# no_name.net
KiCad netlist of a schematic drawn in Altium Designer
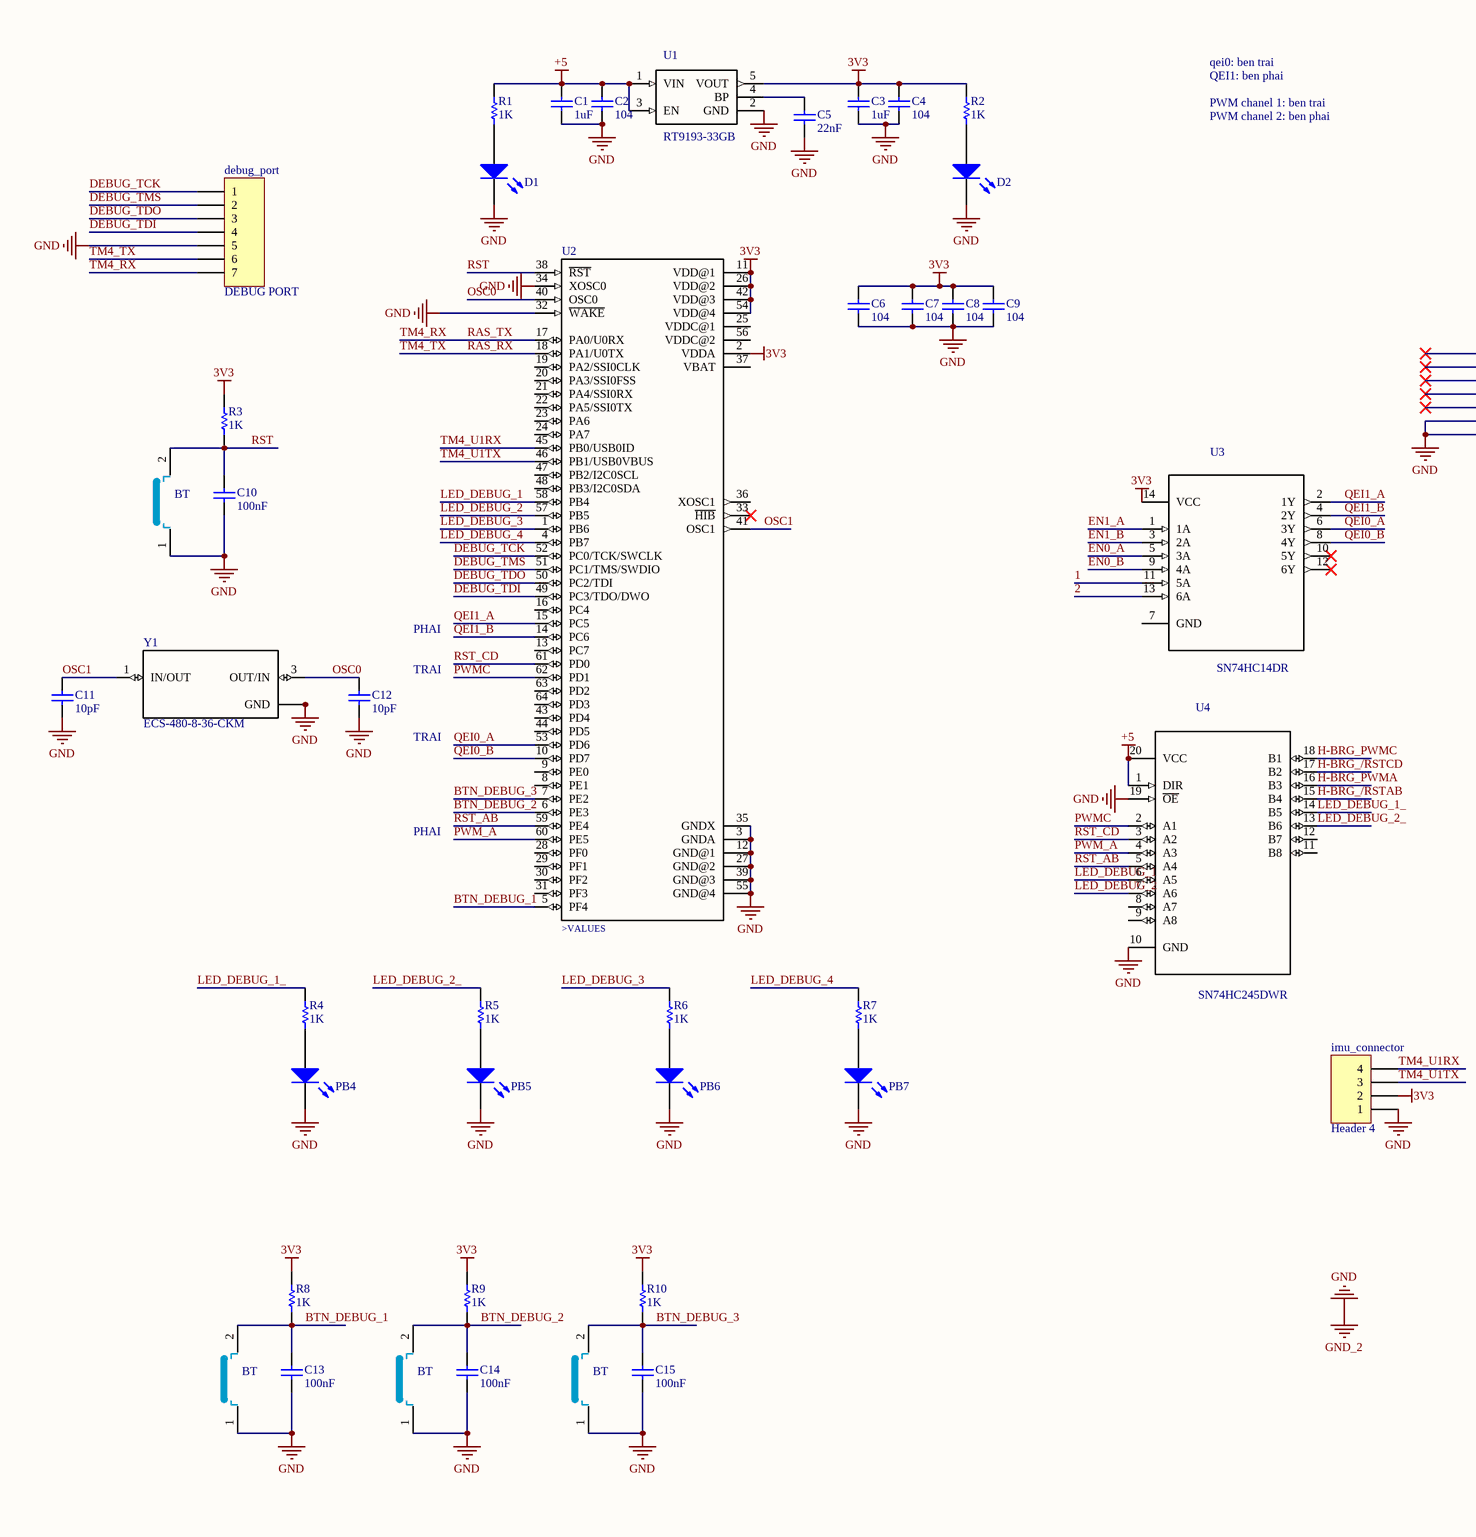
[diagram p0: no_name.SchDoc, left]
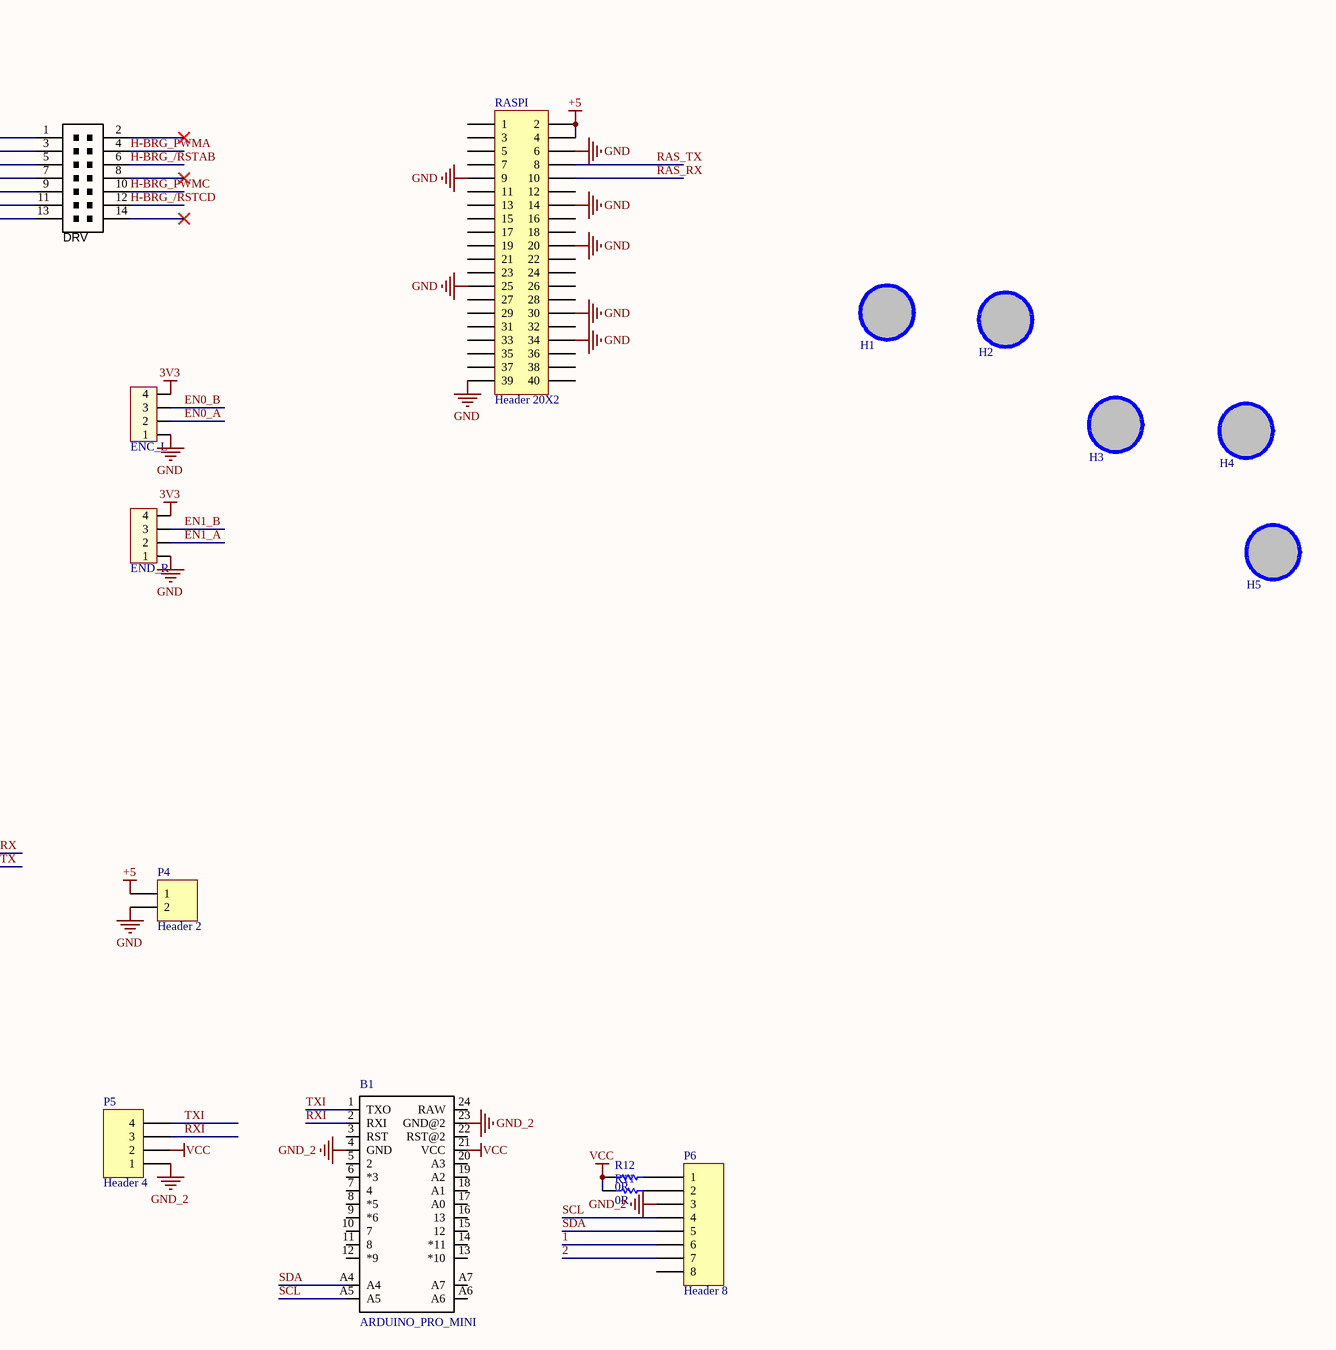
[diagram p1: no_name.SchDoc, right]

(export (version "E")
  (design (tool "Eeschema 10.0.6"))
  (components
    (comp (ref "B1")
      (value "ARDUINO_PRO_MINI")
      (footprint "*ARDUINO_PRO_MINI_ARDUINO_PRO_MINI(Primary)")
      (description "Arduino Pro Mini 328 - 3.3V/8 MHz")
      (fields (field (name "MF") "Arduino") (field (name "MP") "ARDUINO PRO MINI"))
      (libsource (lib "ARDUINO_PRO_MINI") (part "ARDUINO_PRO_MINI"))
    )
    (comp (ref "BT1") (value "BT") (footprint "SW4") (libsource (lib "My library altium") (part "BUTTON")))
    (comp (ref "C1")
      (value "1uF")
      (footprint "CAP-SM-0805")
      (description "Capacitor")
      (fields (field (name "Comment") "Cap Non-Pol SMD"))
      (libsource (lib "PIF_Library") (part "Cap Non-Pol SMD"))
    )
    (comp (ref "C2")
      (value "104")
      (footprint "CAP-SM-0805")
      (description "Capacitor")
      (fields (field (name "Comment") "Cap Non-Pol SMD"))
      (libsource (lib "PIF_Library") (part "Cap Non-Pol SMD"))
    )
    (comp (ref "C3")
      (value "1uF")
      (footprint "CAP-SM-0805")
      (description "Capacitor")
      (fields (field (name "Comment") "Cap Non-Pol SMD"))
      (libsource (lib "PIF_Library") (part "Cap Non-Pol SMD"))
    )
    (comp (ref "C4")
      (value "104")
      (footprint "CAP-SM-0805")
      (description "Capacitor")
      (fields (field (name "Comment") "Cap Non-Pol SMD"))
      (libsource (lib "PIF_Library") (part "Cap Non-Pol SMD"))
    )
    (comp (ref "C5")
      (value "22nF")
      (footprint "CAP-SM-0805")
      (description "Capacitor")
      (fields (field (name "Comment") "Cap Non-Pol SMD"))
      (libsource (lib "PIF_Library") (part "Cap Non-Pol SMD"))
    )
    (comp (ref "C6")
      (value "104")
      (footprint "CAP-SM-0805")
      (description "Capacitor")
      (fields (field (name "Comment") "Cap Non-Pol SMD"))
      (libsource (lib "PIF_Library") (part "Cap Non-Pol SMD"))
    )
    (comp (ref "C7")
      (value "104")
      (footprint "CAP-SM-0805")
      (description "Capacitor")
      (fields (field (name "Comment") "Cap Non-Pol SMD"))
      (libsource (lib "PIF_Library") (part "Cap Non-Pol SMD"))
    )
    (comp (ref "C8")
      (value "104")
      (footprint "CAP-SM-0805")
      (description "Capacitor")
      (fields (field (name "Comment") "Cap Non-Pol SMD"))
      (libsource (lib "PIF_Library") (part "Cap Non-Pol SMD"))
    )
    (comp (ref "C9")
      (value "104")
      (footprint "CAP-SM-0805")
      (description "Capacitor")
      (fields (field (name "Comment") "Cap Non-Pol SMD"))
      (libsource (lib "PIF_Library") (part "Cap Non-Pol SMD"))
    )
    (comp (ref "C10")
      (value "100nF")
      (footprint "CAP-SM-0805")
      (description "Capacitor")
      (fields (field (name "Comment") "Cap Non-Pol SMD"))
      (libsource (lib "PIF_Library") (part "Cap Non-Pol SMD"))
    )
    (comp (ref "C11")
      (value "10pF")
      (footprint "CAP-SM-0805")
      (description "Capacitor")
      (fields (field (name "Comment") "Cap Non-Pol SMD"))
      (libsource (lib "PIF_Library") (part "Cap Non-Pol SMD"))
    )
    (comp (ref "C12")
      (value "10pF")
      (footprint "CAP-SM-0805")
      (description "Capacitor")
      (fields (field (name "Comment") "Cap Non-Pol SMD"))
      (libsource (lib "PIF_Library") (part "Cap Non-Pol SMD"))
    )
    (comp (ref "C13")
      (value "100nF")
      (footprint "CAP-SM-0805")
      (description "Capacitor")
      (fields (field (name "Comment") "Cap Non-Pol SMD"))
      (libsource (lib "PIF_Library") (part "Cap Non-Pol SMD"))
    )
    (comp (ref "C14")
      (value "100nF")
      (footprint "CAP-SM-0805")
      (description "Capacitor")
      (fields (field (name "Comment") "Cap Non-Pol SMD"))
      (libsource (lib "PIF_Library") (part "Cap Non-Pol SMD"))
    )
    (comp (ref "C15")
      (value "100nF")
      (footprint "CAP-SM-0805")
      (description "Capacitor")
      (fields (field (name "Comment") "Cap Non-Pol SMD"))
      (libsource (lib "PIF_Library") (part "Cap Non-Pol SMD"))
    )
    (comp (ref "D1")
      (value "LED SMD")
      (footprint "LED_0805_Blue")
      (description "LED")
      (libsource (lib "PIF_Library") (part "LED SMD"))
    )
    (comp (ref "D2")
      (value "LED SMD")
      (footprint "LED_0805_Blue")
      (description "LED")
      (libsource (lib "PIF_Library") (part "LED SMD"))
    )
    (comp (ref "debug_port")
      (value "DEBUG PORT")
      (footprint "HDR1X7")
      (description "Header, 7-Pin")
      (fields (field (name "PUBLISHER") "Altium Limited"))
      (libsource (lib "Miscellaneous Connectors") (part "Header 7"))
    )
    (comp (ref "DRV")
      (value "shrouded box header")
      (footprint "14P_PCB_HEADER_BRD_MNT_RA")
      (description "Header THD 14 POS Double-row right-angle 2.54mm pitch")
      (libsource (lib "tuanti1997qn") (part "CONN_HEADER_2x7P_RA_0.100in_Male"))
    )
    (comp (ref "ENC_L")
      (value "ENC_L")
      (footprint "CON4")
      (description "Connector 4")
      (libsource (lib "tuanti1997qn") (part "Con4"))
    )
    (comp (ref "END_R")
      (value "END_R")
      (footprint "CON4")
      (description "Connector 4")
      (libsource (lib "tuanti1997qn") (part "Con4"))
    )
    (comp (ref "H1")
      (value "Hole")
      (footprint "LO KHOAN 3MM")
      (description "Hole 3mm")
      (libsource (lib "PIF_Library") (part "Hole"))
    )
    (comp (ref "H2")
      (value "Hole")
      (footprint "LO KHOAN 3MM")
      (description "Hole 3mm")
      (libsource (lib "PIF_Library") (part "Hole"))
    )
    (comp (ref "H3")
      (value "Hole")
      (footprint "LO KHOAN 3MM")
      (description "Hole 3mm")
      (libsource (lib "PIF_Library") (part "Hole"))
    )
    (comp (ref "H4")
      (value "Hole")
      (footprint "LO KHOAN 3MM")
      (description "Hole 3mm")
      (libsource (lib "PIF_Library") (part "Hole"))
    )
    (comp (ref "H5")
      (value "Hole")
      (footprint "LO KHOAN 3MM")
      (description "Hole 3mm")
      (libsource (lib "PIF_Library") (part "Hole"))
    )
    (comp (ref "imu_connector")
      (value "Header 4")
      (footprint "HDR1X4")
      (description "Header, 4-Pin")
      (fields (field (name "PUBLISHER") "Altium Limited"))
      (libsource (lib "Miscellaneous Connectors") (part "Header 4"))
    )
    (comp (ref "P4")
      (value "Header 2")
      (footprint "HDR1X2")
      (description "Header, 2-Pin")
      (fields (field (name "PUBLISHER") "Altium Limited"))
      (libsource (lib "Miscellaneous Connectors") (part "Header 2"))
    )
    (comp (ref "P5")
      (value "Header 4")
      (footprint "HDR1X4")
      (description "Header, 4-Pin")
      (fields (field (name "PUBLISHER") "Altium Limited"))
      (libsource (lib "Miscellaneous Connectors") (part "Header 4"))
    )
    (comp (ref "P6")
      (value "Header 8")
      (footprint "HDR1X8")
      (description "Header, 8-Pin")
      (fields (field (name "PUBLISHER") "Altium Limited"))
      (libsource (lib "Miscellaneous Connectors") (part "Header 8"))
    )
    (comp (ref "PB4")
      (value "LED SMD")
      (footprint "LED_0805_Blue")
      (description "LED")
      (libsource (lib "PIF_Library") (part "LED SMD"))
    )
    (comp (ref "PB5")
      (value "LED SMD")
      (footprint "LED_0805_Blue")
      (description "LED")
      (libsource (lib "PIF_Library") (part "LED SMD"))
    )
    (comp (ref "PB6")
      (value "LED SMD")
      (footprint "LED_0805_Blue")
      (description "LED")
      (libsource (lib "PIF_Library") (part "LED SMD"))
    )
    (comp (ref "PB7")
      (value "LED SMD")
      (footprint "LED_0805_Blue")
      (description "LED")
      (libsource (lib "PIF_Library") (part "LED SMD"))
    )
    (comp (ref "PE2") (value "BT") (footprint "SW4") (libsource (lib "My library altium") (part "BUTTON")))
    (comp (ref "PE3") (value "BT") (footprint "SW4") (libsource (lib "My library altium") (part "BUTTON")))
    (comp (ref "PF4") (value "BT") (footprint "SW4") (libsource (lib "My library altium") (part "BUTTON")))
    (comp (ref "R1")
      (value "1K")
      (footprint "RES-SM-0805")
      (description "Resistor")
      (fields (field (name "Comment") "RESISTOR SMD"))
      (libsource (lib "PIF_Library") (part "RESISTOR SMD"))
    )
    (comp (ref "R2")
      (value "1K")
      (footprint "RES-SM-0805")
      (description "Resistor")
      (fields (field (name "Comment") "RESISTOR SMD"))
      (libsource (lib "PIF_Library") (part "RESISTOR SMD"))
    )
    (comp (ref "R3")
      (value "1K")
      (footprint "RES-SM-0805")
      (description "Resistor")
      (fields (field (name "Comment") "RESISTOR SMD"))
      (libsource (lib "PIF_Library") (part "RESISTOR SMD"))
    )
    (comp (ref "R4")
      (value "1K")
      (footprint "RES-SM-0805")
      (description "Resistor")
      (fields (field (name "Comment") "RESISTOR SMD"))
      (libsource (lib "PIF_Library") (part "RESISTOR SMD"))
    )
    (comp (ref "R5")
      (value "1K")
      (footprint "RES-SM-0805")
      (description "Resistor")
      (fields (field (name "Comment") "RESISTOR SMD"))
      (libsource (lib "PIF_Library") (part "RESISTOR SMD"))
    )
    (comp (ref "R6")
      (value "1K")
      (footprint "RES-SM-0805")
      (description "Resistor")
      (fields (field (name "Comment") "RESISTOR SMD"))
      (libsource (lib "PIF_Library") (part "RESISTOR SMD"))
    )
    (comp (ref "R7")
      (value "1K")
      (footprint "RES-SM-0805")
      (description "Resistor")
      (fields (field (name "Comment") "RESISTOR SMD"))
      (libsource (lib "PIF_Library") (part "RESISTOR SMD"))
    )
    (comp (ref "R8")
      (value "1K")
      (footprint "RES-SM-0805")
      (description "Resistor")
      (fields (field (name "Comment") "RESISTOR SMD"))
      (libsource (lib "PIF_Library") (part "RESISTOR SMD"))
    )
    (comp (ref "R9")
      (value "1K")
      (footprint "RES-SM-0805")
      (description "Resistor")
      (fields (field (name "Comment") "RESISTOR SMD"))
      (libsource (lib "PIF_Library") (part "RESISTOR SMD"))
    )
    (comp (ref "R10")
      (value "1K")
      (footprint "RES-SM-0805")
      (description "Resistor")
      (fields (field (name "Comment") "RESISTOR SMD"))
      (libsource (lib "PIF_Library") (part "RESISTOR SMD"))
    )
    (comp (ref "R11")
      (value "0R")
      (footprint "RES-SM-0805")
      (description "Resistor")
      (fields (field (name "Comment") "RESISTOR SMD"))
      (libsource (lib "PIF_Library") (part "RESISTOR SMD"))
    )
    (comp (ref "R12")
      (value "0R")
      (footprint "RES-SM-0805")
      (description "Resistor")
      (fields (field (name "Comment") "RESISTOR SMD"))
      (libsource (lib "PIF_Library") (part "RESISTOR SMD"))
    )
    (comp (ref "RASPI")
      (value "Header 20X2")
      (footprint "HDR2X20")
      (description "Header, 20-Pin, Dual row")
      (fields (field (name "PUBLISHER") "Altium Limited"))
      (libsource (lib "Miscellaneous Connectors") (part "Header 20X2"))
    )
    (comp (ref "U1")
      (value "RT9193-33GB")
      (footprint "*SOT94P279X129-5N")
      (description "RT9193 Series 300 mA 3.3 V Ultra-Low Noise Ultra-Fast CMOS LDO Regulator-SC-70-5")
      (fields (field (name "MF") "Richtek USA"))
      (libsource (lib "RT9193-33GB") (part "RT9193-33GB"))
    )
    (comp (ref "U2")
      (value "TM4C123GH6PMI")
      (footprint "*QFP50P1200X1200X160-64N")
      (description "MCU 32-Bit Tiva C ARM Cortex M4F RISC 256KB Flash 1.2V/3.3V 64-Pin LQFP Tray/Tube")
      (fields (field (name "MF") "Texas Instruments"))
      (libsource (lib "TM4C123GH6PMI") (part "TM4C123GH6PMI"))
    )
    (comp (ref "U3")
      (value "SN74HC14DR")
      (footprint "*SOIC127P600X175-14N")
      (description "Inverter Schmitt Trigger 6-Element CMOS 14-Pin SOIC T/R")
      (fields (field (name "MF") "Texas Instruments"))
      (libsource (lib "SN74HC14DR") (part "SN74HC14DR"))
    )
    (comp (ref "U4")
      (value "SN74HC245DWR")
      (footprint "*SOIC127P1030X265-20N")
      (description "Logic IC - Receiver, transceiver Texas Instruments SN74HC245DWR SOIC 20")
      (fields (field (name "MF") "Texas Instruments"))
      (libsource (lib "SN74HC245DWR") (part "SN74HC245DWR"))
    )
    (comp (ref "Y1")
      (value "ECS-480-8-36-CKM")
      (footprint "*XTAL_ECS-480-8-36-CKM")
      (fields (field (name "MF") "ECS Inc."))
      (libsource (lib "ECS-480-8-36-CKM") (part "ECS-480-8-36-CKM"))
    )
  )
  (nets
    (net (code "1") (name "+5") (class "Default")
      (node (ref "C1") (pin "2") (pinfunction "2_2") (pintype "passive"))
      (node (ref "C2") (pin "2") (pinfunction "2_2") (pintype "passive"))
      (node (ref "P4") (pin "1") (pinfunction "1_1") (pintype "passive"))
      (node (ref "R1") (pin "2") (pinfunction "2_2") (pintype "passive"))
      (node (ref "RASPI") (pin "2") (pinfunction "2_2") (pintype "passive"))
      (node (ref "RASPI") (pin "4") (pinfunction "4_4") (pintype "passive"))
      (node (ref "U1") (pin "1") (pinfunction "VIN_1") (pintype "input"))
      (node (ref "U1") (pin "3") (pinfunction "EN_3") (pintype "input"))
      (node (ref "U4") (pin "1") (pinfunction "DIR_1") (pintype "input"))
      (node (ref "U4") (pin "20") (pinfunction "VCC_20") (pintype "power_in"))
    )
    (net (code "2") (name "/1") (class "Default")
      (node (ref "P6") (pin "6") (pinfunction "6_6") (pintype "passive"))
      (node (ref "U3") (pin "11") (pinfunction "5A_11") (pintype "input"))
    )
    (net (code "3") (name "/2") (class "Default")
      (node (ref "P6") (pin "7") (pinfunction "7_7") (pintype "passive"))
      (node (ref "U3") (pin "13") (pinfunction "6A_13") (pintype "input"))
    )
    (net (code "4") (name "/BTN_DEBUG_1") (class "Default")
      (node (ref "C13") (pin "2") (pinfunction "2_2") (pintype "passive"))
      (node (ref "PF4") (pin "2") (pinfunction "2_2") (pintype "passive"))
      (node (ref "R8") (pin "1") (pinfunction "1_1") (pintype "passive"))
      (node (ref "U2") (pin "5") (pinfunction "PF4_5") (pintype "bidirectional"))
    )
    (net (code "5") (name "/BTN_DEBUG_2") (class "Default")
      (node (ref "C14") (pin "2") (pinfunction "2_2") (pintype "passive"))
      (node (ref "PE3") (pin "2") (pinfunction "2_2") (pintype "passive"))
      (node (ref "R9") (pin "1") (pinfunction "1_1") (pintype "passive"))
      (node (ref "U2") (pin "6") (pinfunction "PE3_6") (pintype "bidirectional"))
    )
    (net (code "6") (name "/BTN_DEBUG_3") (class "Default")
      (node (ref "C15") (pin "2") (pinfunction "2_2") (pintype "passive"))
      (node (ref "PE2") (pin "2") (pinfunction "2_2") (pintype "passive"))
      (node (ref "R10") (pin "1") (pinfunction "1_1") (pintype "passive"))
      (node (ref "U2") (pin "7") (pinfunction "PE2_7") (pintype "bidirectional"))
    )
    (net (code "7") (name "/DEBUG_TCK") (class "Default")
      (node (ref "U2") (pin "52") (pinfunction "PC0/TCK/SWCLK_52") (pintype "bidirectional"))
      (node (ref "debug_port") (pin "1") (pinfunction "1_1") (pintype "passive"))
    )
    (net (code "8") (name "/DEBUG_TDI") (class "Default")
      (node (ref "U2") (pin "49") (pinfunction "PC3/TDO/DWO_49") (pintype "bidirectional"))
      (node (ref "debug_port") (pin "4") (pinfunction "4_4") (pintype "passive"))
    )
    (net (code "9") (name "/DEBUG_TDO") (class "Default")
      (node (ref "U2") (pin "50") (pinfunction "PC2/TDI_50") (pintype "bidirectional"))
      (node (ref "debug_port") (pin "3") (pinfunction "3_3") (pintype "passive"))
    )
    (net (code "10") (name "/DEBUG_TMS") (class "Default")
      (node (ref "U2") (pin "51") (pinfunction "PC1/TMS/SWDIO_51") (pintype "bidirectional"))
      (node (ref "debug_port") (pin "2") (pinfunction "2_2") (pintype "passive"))
    )
    (net (code "11") (name "/EN0_A") (class "Default")
      (node (ref "ENC_L") (pin "2") (pinfunction "2_2") (pintype "passive"))
      (node (ref "U3") (pin "5") (pinfunction "3A_5") (pintype "input"))
    )
    (net (code "12") (name "/EN0_B") (class "Default")
      (node (ref "ENC_L") (pin "3") (pinfunction "3_3") (pintype "passive"))
      (node (ref "U3") (pin "9") (pinfunction "4A_9") (pintype "input"))
    )
    (net (code "13") (name "/EN1_A") (class "Default")
      (node (ref "END_R") (pin "2") (pinfunction "2_2") (pintype "passive"))
      (node (ref "U3") (pin "1") (pinfunction "1A_1") (pintype "input"))
    )
    (net (code "14") (name "/EN1_B") (class "Default")
      (node (ref "END_R") (pin "3") (pinfunction "3_3") (pintype "passive"))
      (node (ref "U3") (pin "3") (pinfunction "2A_3") (pintype "input"))
    )
    (net (code "15") (name "/H-BRG_PWMA") (class "Default")
      (node (ref "DRV") (pin "4") (pinfunction "4_4") (pintype "passive"))
      (node (ref "U4") (pin "16") (pinfunction "B3_16") (pintype "bidirectional"))
    )
    (net (code "16") (name "/H-BRG_PWMC") (class "Default")
      (node (ref "DRV") (pin "10") (pinfunction "10_10") (pintype "passive"))
      (node (ref "U4") (pin "18") (pinfunction "B1_18") (pintype "bidirectional"))
    )
    (net (code "17") (name "/H-BRG_{slash}RSTAB") (class "Default")
      (node (ref "DRV") (pin "6") (pinfunction "6_6") (pintype "passive"))
      (node (ref "U4") (pin "15") (pinfunction "B4_15") (pintype "bidirectional"))
    )
    (net (code "18") (name "/H-BRG_{slash}RSTCD") (class "Default")
      (node (ref "DRV") (pin "12") (pinfunction "12_12") (pintype "passive"))
      (node (ref "U4") (pin "17") (pinfunction "B2_17") (pintype "bidirectional"))
    )
    (net (code "19") (name "/LED_DEBUG_1") (class "Default")
      (node (ref "U2") (pin "58") (pinfunction "PB4_58") (pintype "bidirectional"))
      (node (ref "U4") (pin "6") (pinfunction "A5_6") (pintype "bidirectional"))
    )
    (net (code "20") (name "/LED_DEBUG_1_") (class "Default")
      (node (ref "R4") (pin "2") (pinfunction "2_2") (pintype "passive"))
      (node (ref "U4") (pin "14") (pinfunction "B5_14") (pintype "bidirectional"))
    )
    (net (code "21") (name "/LED_DEBUG_2") (class "Default")
      (node (ref "U2") (pin "57") (pinfunction "PB5_57") (pintype "bidirectional"))
      (node (ref "U4") (pin "7") (pinfunction "A6_7") (pintype "bidirectional"))
    )
    (net (code "22") (name "/LED_DEBUG_2_") (class "Default")
      (node (ref "R5") (pin "2") (pinfunction "2_2") (pintype "passive"))
      (node (ref "U4") (pin "13") (pinfunction "B6_13") (pintype "bidirectional"))
    )
    (net (code "23") (name "/LED_DEBUG_3") (class "Default")
      (node (ref "R6") (pin "2") (pinfunction "2_2") (pintype "passive"))
      (node (ref "U2") (pin "1") (pinfunction "PB6_1") (pintype "bidirectional"))
    )
    (net (code "24") (name "/LED_DEBUG_4") (class "Default")
      (node (ref "R7") (pin "2") (pinfunction "2_2") (pintype "passive"))
      (node (ref "U2") (pin "4") (pinfunction "PB7_4") (pintype "bidirectional"))
    )
    (net (code "25") (name "/OSC0") (class "Default")
      (node (ref "C12") (pin "2") (pinfunction "2_2") (pintype "passive"))
      (node (ref "U2") (pin "40") (pinfunction "OSC0_40") (pintype "input"))
      (node (ref "Y1") (pin "3") (pinfunction "OUT/IN_3") (pintype "bidirectional"))
    )
    (net (code "26") (name "/OSC1") (class "Default")
      (node (ref "C11") (pin "2") (pinfunction "2_2") (pintype "passive"))
      (node (ref "U2") (pin "41") (pinfunction "OSC1_41") (pintype "output"))
      (node (ref "Y1") (pin "1") (pinfunction "IN/OUT_1") (pintype "bidirectional"))
    )
    (net (code "27") (name "/PWMC") (class "Default")
      (node (ref "U2") (pin "62") (pinfunction "PD1_62") (pintype "bidirectional"))
      (node (ref "U4") (pin "2") (pinfunction "A1_2") (pintype "bidirectional"))
    )
    (net (code "28") (name "/PWM_A") (class "Default")
      (node (ref "U2") (pin "60") (pinfunction "PE5_60") (pintype "bidirectional"))
      (node (ref "U4") (pin "4") (pinfunction "A3_4") (pintype "bidirectional"))
    )
    (net (code "29") (name "/QEI0_A") (class "Default")
      (node (ref "U2") (pin "53") (pinfunction "PD6_53") (pintype "bidirectional"))
      (node (ref "U3") (pin "6") (pinfunction "3Y_6") (pintype "output"))
    )
    (net (code "30") (name "/QEI0_B") (class "Default")
      (node (ref "U2") (pin "10") (pinfunction "PD7_10") (pintype "bidirectional"))
      (node (ref "U3") (pin "8") (pinfunction "4Y_8") (pintype "output"))
    )
    (net (code "31") (name "/QEI1_A") (class "Default")
      (node (ref "U2") (pin "15") (pinfunction "PC5_15") (pintype "bidirectional"))
      (node (ref "U3") (pin "2") (pinfunction "1Y_2") (pintype "output"))
    )
    (net (code "32") (name "/QEI1_B") (class "Default")
      (node (ref "U2") (pin "14") (pinfunction "PC6_14") (pintype "bidirectional"))
      (node (ref "U3") (pin "4") (pinfunction "2Y_4") (pintype "output"))
    )
    (net (code "33") (name "/RAS_RX") (class "Default")
      (node (ref "RASPI") (pin "10") (pinfunction "10_10") (pintype "passive"))
      (node (ref "U2") (pin "18") (pinfunction "PA1/U0TX_18") (pintype "bidirectional"))
      (node (ref "debug_port") (pin "6") (pinfunction "6_6") (pintype "passive"))
    )
    (net (code "34") (name "/RAS_TX") (class "Default")
      (node (ref "RASPI") (pin "8") (pinfunction "8_8") (pintype "passive"))
      (node (ref "U2") (pin "17") (pinfunction "PA0/U0RX_17") (pintype "bidirectional"))
      (node (ref "debug_port") (pin "7") (pinfunction "7_7") (pintype "passive"))
    )
    (net (code "35") (name "/RST") (class "Default")
      (node (ref "BT1") (pin "2") (pinfunction "2_2") (pintype "passive"))
      (node (ref "C10") (pin "2") (pinfunction "2_2") (pintype "passive"))
      (node (ref "R3") (pin "1") (pinfunction "1_1") (pintype "passive"))
      (node (ref "U2") (pin "38") (pinfunction "~{RST}_38") (pintype "input"))
    )
    (net (code "36") (name "/RST_AB") (class "Default")
      (node (ref "U2") (pin "59") (pinfunction "PE4_59") (pintype "bidirectional"))
      (node (ref "U4") (pin "5") (pinfunction "A4_5") (pintype "bidirectional"))
    )
    (net (code "37") (name "/RST_CD") (class "Default")
      (node (ref "U2") (pin "61") (pinfunction "PD0_61") (pintype "bidirectional"))
      (node (ref "U4") (pin "3") (pinfunction "A2_3") (pintype "bidirectional"))
    )
    (net (code "38") (name "/RXI") (class "Default")
      (node (ref "B1") (pin "2") (pinfunction "RXI_2") (pintype "bidirectional"))
      (node (ref "P5") (pin "3") (pinfunction "3_3") (pintype "passive"))
    )
    (net (code "39") (name "/SCL") (class "Default")
      (node (ref "B1") (pin "A5") (pinfunction "A5_A5") (pintype "bidirectional"))
      (node (ref "P6") (pin "4") (pinfunction "4_4") (pintype "passive"))
    )
    (net (code "40") (name "/SDA") (class "Default")
      (node (ref "B1") (pin "A4") (pinfunction "A4_A4") (pintype "bidirectional"))
      (node (ref "P6") (pin "5") (pinfunction "5_5") (pintype "passive"))
    )
    (net (code "41") (name "/TM4_U1RX") (class "Default")
      (node (ref "U2") (pin "45") (pinfunction "PB0/USB0ID_45") (pintype "bidirectional"))
      (node (ref "imu_connector") (pin "4") (pinfunction "4_4") (pintype "passive"))
    )
    (net (code "42") (name "/TM4_U1TX") (class "Default")
      (node (ref "U2") (pin "46") (pinfunction "PB1/USB0VBUS_46") (pintype "bidirectional"))
      (node (ref "imu_connector") (pin "3") (pinfunction "3_3") (pintype "passive"))
    )
    (net (code "43") (name "/TXI") (class "Default")
      (node (ref "B1") (pin "1") (pinfunction "TXO_1") (pintype "bidirectional"))
      (node (ref "P5") (pin "4") (pinfunction "4_4") (pintype "passive"))
    )
    (net (code "44") (name "3V3") (class "Default")
      (node (ref "C3") (pin "2") (pinfunction "2_2") (pintype "passive"))
      (node (ref "C4") (pin "2") (pinfunction "2_2") (pintype "passive"))
      (node (ref "C6") (pin "2") (pinfunction "2_2") (pintype "passive"))
      (node (ref "C7") (pin "2") (pinfunction "2_2") (pintype "passive"))
      (node (ref "C8") (pin "2") (pinfunction "2_2") (pintype "passive"))
      (node (ref "C9") (pin "2") (pinfunction "2_2") (pintype "passive"))
      (node (ref "ENC_L") (pin "4") (pinfunction "4_4") (pintype "passive"))
      (node (ref "END_R") (pin "4") (pinfunction "4_4") (pintype "passive"))
      (node (ref "R10") (pin "2") (pinfunction "2_2") (pintype "passive"))
      (node (ref "R2") (pin "2") (pinfunction "2_2") (pintype "passive"))
      (node (ref "R3") (pin "2") (pinfunction "2_2") (pintype "passive"))
      (node (ref "R8") (pin "2") (pinfunction "2_2") (pintype "passive"))
      (node (ref "R9") (pin "2") (pinfunction "2_2") (pintype "passive"))
      (node (ref "U1") (pin "5") (pinfunction "VOUT_5") (pintype "output"))
      (node (ref "U2") (pin "11") (pinfunction "VDD@1_11") (pintype "power_in"))
      (node (ref "U2") (pin "2") (pinfunction "VDDA_2") (pintype "power_in"))
      (node (ref "U2") (pin "26") (pinfunction "VDD@2_26") (pintype "power_in"))
      (node (ref "U2") (pin "42") (pinfunction "VDD@3_42") (pintype "power_in"))
      (node (ref "U2") (pin "54") (pinfunction "VDD@4_54") (pintype "power_in"))
      (node (ref "U3") (pin "14") (pinfunction "VCC_14") (pintype "power_in"))
      (node (ref "imu_connector") (pin "2") (pinfunction "2_2") (pintype "passive"))
    )
    (net (code "45") (name "GND") (class "Default")
      (node (ref "B1") (pin "23") (pinfunction "GND@2_23") (pintype "power_in"))
      (node (ref "B1") (pin "4") (pinfunction "GND_4") (pintype "power_in"))
      (node (ref "BT1") (pin "1") (pinfunction "1_1") (pintype "passive"))
      (node (ref "C1") (pin "1") (pinfunction "1_1") (pintype "passive"))
      (node (ref "C10") (pin "1") (pinfunction "1_1") (pintype "passive"))
      (node (ref "C11") (pin "1") (pinfunction "1_1") (pintype "passive"))
      (node (ref "C12") (pin "1") (pinfunction "1_1") (pintype "passive"))
      (node (ref "C13") (pin "1") (pinfunction "1_1") (pintype "passive"))
      (node (ref "C14") (pin "1") (pinfunction "1_1") (pintype "passive"))
      (node (ref "C15") (pin "1") (pinfunction "1_1") (pintype "passive"))
      (node (ref "C2") (pin "1") (pinfunction "1_1") (pintype "passive"))
      (node (ref "C3") (pin "1") (pinfunction "1_1") (pintype "passive"))
      (node (ref "C4") (pin "1") (pinfunction "1_1") (pintype "passive"))
      (node (ref "C5") (pin "1") (pinfunction "1_1") (pintype "passive"))
      (node (ref "C6") (pin "1") (pinfunction "1_1") (pintype "passive"))
      (node (ref "C7") (pin "1") (pinfunction "1_1") (pintype "passive"))
      (node (ref "C8") (pin "1") (pinfunction "1_1") (pintype "passive"))
      (node (ref "C9") (pin "1") (pinfunction "1_1") (pintype "passive"))
      (node (ref "D1") (pin "2") (pinfunction "K_2") (pintype "passive"))
      (node (ref "D2") (pin "2") (pinfunction "K_2") (pintype "passive"))
      (node (ref "DRV") (pin "11") (pinfunction "11_11") (pintype "passive"))
      (node (ref "DRV") (pin "13") (pinfunction "13_13") (pintype "passive"))
      (node (ref "ENC_L") (pin "1") (pinfunction "1_1") (pintype "passive"))
      (node (ref "END_R") (pin "1") (pinfunction "1_1") (pintype "passive"))
      (node (ref "P4") (pin "2") (pinfunction "2_2") (pintype "passive"))
      (node (ref "P5") (pin "1") (pinfunction "1_1") (pintype "passive"))
      (node (ref "P6") (pin "3") (pinfunction "3_3") (pintype "passive"))
      (node (ref "PB4") (pin "2") (pinfunction "K_2") (pintype "passive"))
      (node (ref "PB5") (pin "2") (pinfunction "K_2") (pintype "passive"))
      (node (ref "PB6") (pin "2") (pinfunction "K_2") (pintype "passive"))
      (node (ref "PB7") (pin "2") (pinfunction "K_2") (pintype "passive"))
      (node (ref "PE2") (pin "1") (pinfunction "1_1") (pintype "passive"))
      (node (ref "PE3") (pin "1") (pinfunction "1_1") (pintype "passive"))
      (node (ref "PF4") (pin "1") (pinfunction "1_1") (pintype "passive"))
      (node (ref "RASPI") (pin "14") (pinfunction "14_14") (pintype "passive"))
      (node (ref "RASPI") (pin "20") (pinfunction "20_20") (pintype "passive"))
      (node (ref "RASPI") (pin "25") (pinfunction "25_25") (pintype "passive"))
      (node (ref "RASPI") (pin "30") (pinfunction "30_30") (pintype "passive"))
      (node (ref "RASPI") (pin "34") (pinfunction "34_34") (pintype "passive"))
      (node (ref "RASPI") (pin "39") (pinfunction "39_39") (pintype "passive"))
      (node (ref "RASPI") (pin "6") (pinfunction "6_6") (pintype "passive"))
      (node (ref "RASPI") (pin "9") (pinfunction "9_9") (pintype "passive"))
      (node (ref "U1") (pin "2") (pinfunction "GND_2") (pintype "power_in"))
      (node (ref "U2") (pin "12") (pinfunction "GND@1_12") (pintype "power_in"))
      (node (ref "U2") (pin "27") (pinfunction "GND@2_27") (pintype "power_in"))
      (node (ref "U2") (pin "3") (pinfunction "GNDA_3") (pintype "power_in"))
      (node (ref "U2") (pin "32") (pinfunction "~{WAKE}_32") (pintype "input"))
      (node (ref "U2") (pin "34") (pinfunction "XOSC0_34") (pintype "input"))
      (node (ref "U2") (pin "35") (pinfunction "GNDX_35") (pintype "power_in"))
      (node (ref "U2") (pin "39") (pinfunction "GND@3_39") (pintype "power_in"))
      (node (ref "U2") (pin "55") (pinfunction "GND@4_55") (pintype "power_in"))
      (node (ref "U4") (pin "10") (pinfunction "GND_10") (pintype "passive"))
      (node (ref "U4") (pin "19") (pinfunction "~{OE}_19") (pintype "input"))
      (node (ref "Y1") (pin "2") (pinfunction "GND_2") (pintype "power_in"))
      (node (ref "Y1") (pin "4") (pinfunction "GND_4") (pintype "power_in"))
      (node (ref "debug_port") (pin "5") (pinfunction "5_5") (pintype "passive"))
      (node (ref "imu_connector") (pin "1") (pinfunction "1_1") (pintype "passive"))
    )
    (net (code "46") (name "Net-(D1-A)") (class "Default")
      (node (ref "D1") (pin "1") (pinfunction "A_1") (pintype "passive"))
      (node (ref "R1") (pin "1") (pinfunction "1_1") (pintype "passive"))
    )
    (net (code "47") (name "Net-(D2-A)") (class "Default")
      (node (ref "D2") (pin "1") (pinfunction "A_1") (pintype "passive"))
      (node (ref "R2") (pin "1") (pinfunction "1_1") (pintype "passive"))
    )
    (net (code "48") (name "Net-(P6-Pad1)") (class "Default")
      (node (ref "P6") (pin "1") (pinfunction "1_1") (pintype "passive"))
      (node (ref "R12") (pin "2") (pinfunction "2_2") (pintype "passive"))
    )
    (net (code "49") (name "Net-(P6-Pad2)") (class "Default")
      (node (ref "P6") (pin "2") (pinfunction "2_2") (pintype "passive"))
      (node (ref "R11") (pin "2") (pinfunction "2_2") (pintype "passive"))
    )
    (net (code "50") (name "Net-(PB4-A)") (class "Default")
      (node (ref "PB4") (pin "1") (pinfunction "A_1") (pintype "passive"))
      (node (ref "R4") (pin "1") (pinfunction "1_1") (pintype "passive"))
    )
    (net (code "51") (name "Net-(PB5-A)") (class "Default")
      (node (ref "PB5") (pin "1") (pinfunction "A_1") (pintype "passive"))
      (node (ref "R5") (pin "1") (pinfunction "1_1") (pintype "passive"))
    )
    (net (code "52") (name "Net-(PB6-A)") (class "Default")
      (node (ref "PB6") (pin "1") (pinfunction "A_1") (pintype "passive"))
      (node (ref "R6") (pin "1") (pinfunction "1_1") (pintype "passive"))
    )
    (net (code "53") (name "Net-(PB7-A)") (class "Default")
      (node (ref "PB7") (pin "1") (pinfunction "A_1") (pintype "passive"))
      (node (ref "R7") (pin "1") (pinfunction "1_1") (pintype "passive"))
    )
    (net (code "54") (name "Net-(U1-BP)") (class "Default")
      (node (ref "C5") (pin "2") (pinfunction "2_2") (pintype "passive"))
      (node (ref "U1") (pin "4") (pinfunction "BP_4") (pintype "passive"))
    )
    (net (code "55") (name "VCC") (class "Default")
      (node (ref "B1") (pin "21") (pinfunction "VCC_21") (pintype "power_in"))
      (node (ref "P5") (pin "2") (pinfunction "2_2") (pintype "passive"))
      (node (ref "R11") (pin "1") (pinfunction "1_1") (pintype "passive"))
      (node (ref "R12") (pin "1") (pinfunction "1_1") (pintype "passive"))
    )
    (net (code "56") (name "unconnected-(B1-*3-Pad6)") (class "Default")
      (node (ref "B1") (pin "6") (pinfunction "*3_6") (pintype "bidirectional"))
    )
    (net (code "57") (name "unconnected-(B1-*5-Pad8)") (class "Default")
      (node (ref "B1") (pin "8") (pinfunction "*5_8") (pintype "bidirectional"))
    )
    (net (code "58") (name "unconnected-(B1-*6-Pad9)") (class "Default")
      (node (ref "B1") (pin "9") (pinfunction "*6_9") (pintype "bidirectional"))
    )
    (net (code "59") (name "unconnected-(B1-*9-Pad12)") (class "Default")
      (node (ref "B1") (pin "12") (pinfunction "*9_12") (pintype "bidirectional"))
    )
    (net (code "60") (name "unconnected-(B1-*10-Pad13)") (class "Default")
      (node (ref "B1") (pin "13") (pinfunction "*10_13") (pintype "bidirectional"))
    )
    (net (code "61") (name "unconnected-(B1-*11-Pad14)") (class "Default")
      (node (ref "B1") (pin "14") (pinfunction "*11_14") (pintype "bidirectional"))
    )
    (net (code "62") (name "unconnected-(B1-2-Pad5)") (class "Default")
      (node (ref "B1") (pin "5") (pinfunction "2_5") (pintype "bidirectional"))
    )
    (net (code "63") (name "unconnected-(B1-4-Pad7)") (class "Default")
      (node (ref "B1") (pin "7") (pinfunction "4_7") (pintype "bidirectional"))
    )
    (net (code "64") (name "unconnected-(B1-7-Pad10)") (class "Default")
      (node (ref "B1") (pin "10") (pinfunction "7_10") (pintype "bidirectional"))
    )
    (net (code "65") (name "unconnected-(B1-8-Pad11)") (class "Default")
      (node (ref "B1") (pin "11") (pinfunction "8_11") (pintype "bidirectional"))
    )
    (net (code "66") (name "unconnected-(B1-12-Pad15)") (class "Default")
      (node (ref "B1") (pin "15") (pinfunction "12_15") (pintype "bidirectional"))
    )
    (net (code "67") (name "unconnected-(B1-13-Pad16)") (class "Default")
      (node (ref "B1") (pin "16") (pinfunction "13_16") (pintype "bidirectional"))
    )
    (net (code "68") (name "unconnected-(B1-A0-Pad17)") (class "Default")
      (node (ref "B1") (pin "17") (pinfunction "A0_17") (pintype "bidirectional"))
    )
    (net (code "69") (name "unconnected-(B1-A1-Pad18)") (class "Default")
      (node (ref "B1") (pin "18") (pinfunction "A1_18") (pintype "bidirectional"))
    )
    (net (code "70") (name "unconnected-(B1-A2-Pad19)") (class "Default")
      (node (ref "B1") (pin "19") (pinfunction "A2_19") (pintype "bidirectional"))
    )
    (net (code "71") (name "unconnected-(B1-A3-Pad20)") (class "Default")
      (node (ref "B1") (pin "20") (pinfunction "A3_20") (pintype "bidirectional"))
    )
    (net (code "72") (name "unconnected-(B1-PadA6)") (class "Default")
      (node (ref "B1") (pin "A6") (pinfunction "A6_A6") (pintype "bidirectional"))
    )
    (net (code "73") (name "unconnected-(B1-PadA7)") (class "Default")
      (node (ref "B1") (pin "A7") (pinfunction "A7_A7") (pintype "bidirectional"))
    )
    (net (code "74") (name "unconnected-(B1-RAW-Pad24)") (class "Default")
      (node (ref "B1") (pin "24") (pinfunction "RAW_24") (pintype "power_in"))
    )
    (net (code "75") (name "unconnected-(B1-RST-Pad3)") (class "Default")
      (node (ref "B1") (pin "3") (pinfunction "RST_3") (pintype "bidirectional"))
    )
    (net (code "76") (name "unconnected-(B1-RST@2-Pad22)") (class "Default")
      (node (ref "B1") (pin "22") (pinfunction "RST@2_22") (pintype "bidirectional"))
    )
    (net (code "77") (name "unconnected-(DRV-Pad1)") (class "Default")
      (node (ref "DRV") (pin "1") (pinfunction "1_1") (pintype "passive+no_connect"))
    )
    (net (code "78") (name "unconnected-(DRV-Pad2)") (class "Default")
      (node (ref "DRV") (pin "2") (pinfunction "2_2") (pintype "passive+no_connect"))
    )
    (net (code "79") (name "unconnected-(DRV-Pad3)") (class "Default")
      (node (ref "DRV") (pin "3") (pinfunction "3_3") (pintype "passive+no_connect"))
    )
    (net (code "80") (name "unconnected-(DRV-Pad5)") (class "Default")
      (node (ref "DRV") (pin "5") (pinfunction "5_5") (pintype "passive+no_connect"))
    )
    (net (code "81") (name "unconnected-(DRV-Pad7)") (class "Default")
      (node (ref "DRV") (pin "7") (pinfunction "7_7") (pintype "passive+no_connect"))
    )
    (net (code "82") (name "unconnected-(DRV-Pad8)") (class "Default")
      (node (ref "DRV") (pin "8") (pinfunction "8_8") (pintype "passive+no_connect"))
    )
    (net (code "83") (name "unconnected-(DRV-Pad9)") (class "Default")
      (node (ref "DRV") (pin "9") (pinfunction "9_9") (pintype "passive+no_connect"))
    )
    (net (code "84") (name "unconnected-(DRV-Pad14)") (class "Default")
      (node (ref "DRV") (pin "14") (pinfunction "14_14") (pintype "passive+no_connect"))
    )
    (net (code "85") (name "unconnected-(H1-Pad1)") (class "Default")
      (node (ref "H1") (pin "1") (pinfunction "1_1") (pintype "passive"))
    )
    (net (code "86") (name "unconnected-(H2-Pad1)") (class "Default")
      (node (ref "H2") (pin "1") (pinfunction "1_1") (pintype "passive"))
    )
    (net (code "87") (name "unconnected-(H3-Pad1)") (class "Default")
      (node (ref "H3") (pin "1") (pinfunction "1_1") (pintype "passive"))
    )
    (net (code "88") (name "unconnected-(H4-Pad1)") (class "Default")
      (node (ref "H4") (pin "1") (pinfunction "1_1") (pintype "passive"))
    )
    (net (code "89") (name "unconnected-(H5-Pad1)") (class "Default")
      (node (ref "H5") (pin "1") (pinfunction "1_1") (pintype "passive"))
    )
    (net (code "90") (name "unconnected-(P6-Pad8)") (class "Default")
      (node (ref "P6") (pin "8") (pinfunction "8_8") (pintype "passive"))
    )
    (net (code "91") (name "unconnected-(RASPI-Pad1)") (class "Default")
      (node (ref "RASPI") (pin "1") (pinfunction "1_1") (pintype "passive"))
    )
    (net (code "92") (name "unconnected-(RASPI-Pad3)") (class "Default")
      (node (ref "RASPI") (pin "3") (pinfunction "3_3") (pintype "passive"))
    )
    (net (code "93") (name "unconnected-(RASPI-Pad5)") (class "Default")
      (node (ref "RASPI") (pin "5") (pinfunction "5_5") (pintype "passive"))
    )
    (net (code "94") (name "unconnected-(RASPI-Pad7)") (class "Default")
      (node (ref "RASPI") (pin "7") (pinfunction "7_7") (pintype "passive"))
    )
    (net (code "95") (name "unconnected-(RASPI-Pad11)") (class "Default")
      (node (ref "RASPI") (pin "11") (pinfunction "11_11") (pintype "passive"))
    )
    (net (code "96") (name "unconnected-(RASPI-Pad12)") (class "Default")
      (node (ref "RASPI") (pin "12") (pinfunction "12_12") (pintype "passive"))
    )
    (net (code "97") (name "unconnected-(RASPI-Pad13)") (class "Default")
      (node (ref "RASPI") (pin "13") (pinfunction "13_13") (pintype "passive"))
    )
    (net (code "98") (name "unconnected-(RASPI-Pad15)") (class "Default")
      (node (ref "RASPI") (pin "15") (pinfunction "15_15") (pintype "passive"))
    )
    (net (code "99") (name "unconnected-(RASPI-Pad16)") (class "Default")
      (node (ref "RASPI") (pin "16") (pinfunction "16_16") (pintype "passive"))
    )
    (net (code "100") (name "unconnected-(RASPI-Pad17)") (class "Default")
      (node (ref "RASPI") (pin "17") (pinfunction "17_17") (pintype "passive"))
    )
    (net (code "101") (name "unconnected-(RASPI-Pad18)") (class "Default")
      (node (ref "RASPI") (pin "18") (pinfunction "18_18") (pintype "passive"))
    )
    (net (code "102") (name "unconnected-(RASPI-Pad19)") (class "Default")
      (node (ref "RASPI") (pin "19") (pinfunction "19_19") (pintype "passive"))
    )
    (net (code "103") (name "unconnected-(RASPI-Pad21)") (class "Default")
      (node (ref "RASPI") (pin "21") (pinfunction "21_21") (pintype "passive"))
    )
    (net (code "104") (name "unconnected-(RASPI-Pad22)") (class "Default")
      (node (ref "RASPI") (pin "22") (pinfunction "22_22") (pintype "passive"))
    )
    (net (code "105") (name "unconnected-(RASPI-Pad23)") (class "Default")
      (node (ref "RASPI") (pin "23") (pinfunction "23_23") (pintype "passive"))
    )
    (net (code "106") (name "unconnected-(RASPI-Pad24)") (class "Default")
      (node (ref "RASPI") (pin "24") (pinfunction "24_24") (pintype "passive"))
    )
    (net (code "107") (name "unconnected-(RASPI-Pad26)") (class "Default")
      (node (ref "RASPI") (pin "26") (pinfunction "26_26") (pintype "passive"))
    )
    (net (code "108") (name "unconnected-(RASPI-Pad27)") (class "Default")
      (node (ref "RASPI") (pin "27") (pinfunction "27_27") (pintype "passive"))
    )
    (net (code "109") (name "unconnected-(RASPI-Pad28)") (class "Default")
      (node (ref "RASPI") (pin "28") (pinfunction "28_28") (pintype "passive"))
    )
    (net (code "110") (name "unconnected-(RASPI-Pad29)") (class "Default")
      (node (ref "RASPI") (pin "29") (pinfunction "29_29") (pintype "passive"))
    )
    (net (code "111") (name "unconnected-(RASPI-Pad31)") (class "Default")
      (node (ref "RASPI") (pin "31") (pinfunction "31_31") (pintype "passive"))
    )
    (net (code "112") (name "unconnected-(RASPI-Pad32)") (class "Default")
      (node (ref "RASPI") (pin "32") (pinfunction "32_32") (pintype "passive"))
    )
    (net (code "113") (name "unconnected-(RASPI-Pad33)") (class "Default")
      (node (ref "RASPI") (pin "33") (pinfunction "33_33") (pintype "passive"))
    )
    (net (code "114") (name "unconnected-(RASPI-Pad35)") (class "Default")
      (node (ref "RASPI") (pin "35") (pinfunction "35_35") (pintype "passive"))
    )
    (net (code "115") (name "unconnected-(RASPI-Pad36)") (class "Default")
      (node (ref "RASPI") (pin "36") (pinfunction "36_36") (pintype "passive"))
    )
    (net (code "116") (name "unconnected-(RASPI-Pad37)") (class "Default")
      (node (ref "RASPI") (pin "37") (pinfunction "37_37") (pintype "passive"))
    )
    (net (code "117") (name "unconnected-(RASPI-Pad38)") (class "Default")
      (node (ref "RASPI") (pin "38") (pinfunction "38_38") (pintype "passive"))
    )
    (net (code "118") (name "unconnected-(RASPI-Pad40)") (class "Default")
      (node (ref "RASPI") (pin "40") (pinfunction "40_40") (pintype "passive"))
    )
    (net (code "119") (name "unconnected-(U2-PA2{slash}SSI0CLK-Pad19)") (class "Default")
      (node (ref "U2") (pin "19") (pinfunction "PA2/SSI0CLK_19") (pintype "bidirectional"))
    )
    (net (code "120") (name "unconnected-(U2-PA3{slash}SSI0FSS-Pad20)") (class "Default")
      (node (ref "U2") (pin "20") (pinfunction "PA3/SSI0FSS_20") (pintype "bidirectional"))
    )
    (net (code "121") (name "unconnected-(U2-PA4{slash}SSI0RX-Pad21)") (class "Default")
      (node (ref "U2") (pin "21") (pinfunction "PA4/SSI0RX_21") (pintype "bidirectional"))
    )
    (net (code "122") (name "unconnected-(U2-PA5{slash}SSI0TX-Pad22)") (class "Default")
      (node (ref "U2") (pin "22") (pinfunction "PA5/SSI0TX_22") (pintype "bidirectional"))
    )
    (net (code "123") (name "unconnected-(U2-PA6-Pad23)") (class "Default")
      (node (ref "U2") (pin "23") (pinfunction "PA6_23") (pintype "bidirectional"))
    )
    (net (code "124") (name "unconnected-(U2-PA7-Pad24)") (class "Default")
      (node (ref "U2") (pin "24") (pinfunction "PA7_24") (pintype "bidirectional"))
    )
    (net (code "125") (name "unconnected-(U2-PB2{slash}I2C0SCL-Pad47)") (class "Default")
      (node (ref "U2") (pin "47") (pinfunction "PB2/I2C0SCL_47") (pintype "bidirectional"))
    )
    (net (code "126") (name "unconnected-(U2-PB3{slash}I2C0SDA-Pad48)") (class "Default")
      (node (ref "U2") (pin "48") (pinfunction "PB3/I2C0SDA_48") (pintype "bidirectional"))
    )
    (net (code "127") (name "unconnected-(U2-PC4-Pad16)") (class "Default")
      (node (ref "U2") (pin "16") (pinfunction "PC4_16") (pintype "bidirectional"))
    )
    (net (code "128") (name "unconnected-(U2-PC7-Pad13)") (class "Default")
      (node (ref "U2") (pin "13") (pinfunction "PC7_13") (pintype "bidirectional"))
    )
    (net (code "129") (name "unconnected-(U2-PD2-Pad63)") (class "Default")
      (node (ref "U2") (pin "63") (pinfunction "PD2_63") (pintype "bidirectional"))
    )
    (net (code "130") (name "unconnected-(U2-PD3-Pad64)") (class "Default")
      (node (ref "U2") (pin "64") (pinfunction "PD3_64") (pintype "bidirectional"))
    )
    (net (code "131") (name "unconnected-(U2-PD4-Pad43)") (class "Default")
      (node (ref "U2") (pin "43") (pinfunction "PD4_43") (pintype "bidirectional"))
    )
    (net (code "132") (name "unconnected-(U2-PD5-Pad44)") (class "Default")
      (node (ref "U2") (pin "44") (pinfunction "PD5_44") (pintype "bidirectional"))
    )
    (net (code "133") (name "unconnected-(U2-PE0-Pad9)") (class "Default")
      (node (ref "U2") (pin "9") (pinfunction "PE0_9") (pintype "bidirectional"))
    )
    (net (code "134") (name "unconnected-(U2-PE1-Pad8)") (class "Default")
      (node (ref "U2") (pin "8") (pinfunction "PE1_8") (pintype "bidirectional"))
    )
    (net (code "135") (name "unconnected-(U2-PF0-Pad28)") (class "Default")
      (node (ref "U2") (pin "28") (pinfunction "PF0_28") (pintype "bidirectional"))
    )
    (net (code "136") (name "unconnected-(U2-PF1-Pad29)") (class "Default")
      (node (ref "U2") (pin "29") (pinfunction "PF1_29") (pintype "bidirectional"))
    )
    (net (code "137") (name "unconnected-(U2-PF2-Pad30)") (class "Default")
      (node (ref "U2") (pin "30") (pinfunction "PF2_30") (pintype "bidirectional"))
    )
    (net (code "138") (name "unconnected-(U2-PF3-Pad31)") (class "Default")
      (node (ref "U2") (pin "31") (pinfunction "PF3_31") (pintype "bidirectional"))
    )
    (net (code "139") (name "unconnected-(U2-VBAT-Pad37)") (class "Default")
      (node (ref "U2") (pin "37") (pinfunction "VBAT_37") (pintype "power_in"))
    )
    (net (code "140") (name "unconnected-(U2-VDDC@1-Pad25)") (class "Default")
      (node (ref "U2") (pin "25") (pinfunction "VDDC@1_25") (pintype "power_in"))
    )
    (net (code "141") (name "unconnected-(U2-VDDC@2-Pad56)") (class "Default")
      (node (ref "U2") (pin "56") (pinfunction "VDDC@2_56") (pintype "power_in"))
    )
    (net (code "142") (name "unconnected-(U2-XOSC1-Pad36)") (class "Default")
      (node (ref "U2") (pin "36") (pinfunction "XOSC1_36") (pintype "output"))
    )
    (net (code "143") (name "unconnected-(U2-~{HIB}-Pad33)") (class "Default")
      (node (ref "U2") (pin "33") (pinfunction "~{HIB}_33") (pintype "output+no_connect"))
    )
    (net (code "144") (name "unconnected-(U3-5Y-Pad10)") (class "Default")
      (node (ref "U3") (pin "10") (pinfunction "5Y_10") (pintype "output+no_connect"))
    )
    (net (code "145") (name "unconnected-(U3-6Y-Pad12)") (class "Default")
      (node (ref "U3") (pin "12") (pinfunction "6Y_12") (pintype "output+no_connect"))
    )
    (net (code "146") (name "unconnected-(U3-GND-Pad7)") (class "Default")
      (node (ref "U3") (pin "7") (pinfunction "GND_7") (pintype "passive"))
    )
    (net (code "147") (name "unconnected-(U4-A7-Pad8)") (class "Default")
      (node (ref "U4") (pin "8") (pinfunction "A7_8") (pintype "bidirectional"))
    )
    (net (code "148") (name "unconnected-(U4-A8-Pad9)") (class "Default")
      (node (ref "U4") (pin "9") (pinfunction "A8_9") (pintype "bidirectional"))
    )
    (net (code "149") (name "unconnected-(U4-B7-Pad12)") (class "Default")
      (node (ref "U4") (pin "12") (pinfunction "B7_12") (pintype "bidirectional"))
    )
    (net (code "150") (name "unconnected-(U4-B8-Pad11)") (class "Default")
      (node (ref "U4") (pin "11") (pinfunction "B8_11") (pintype "bidirectional"))
    )
  )
)
